# Main_Board.net
KiCad netlist of a schematic drawn in EAGLE
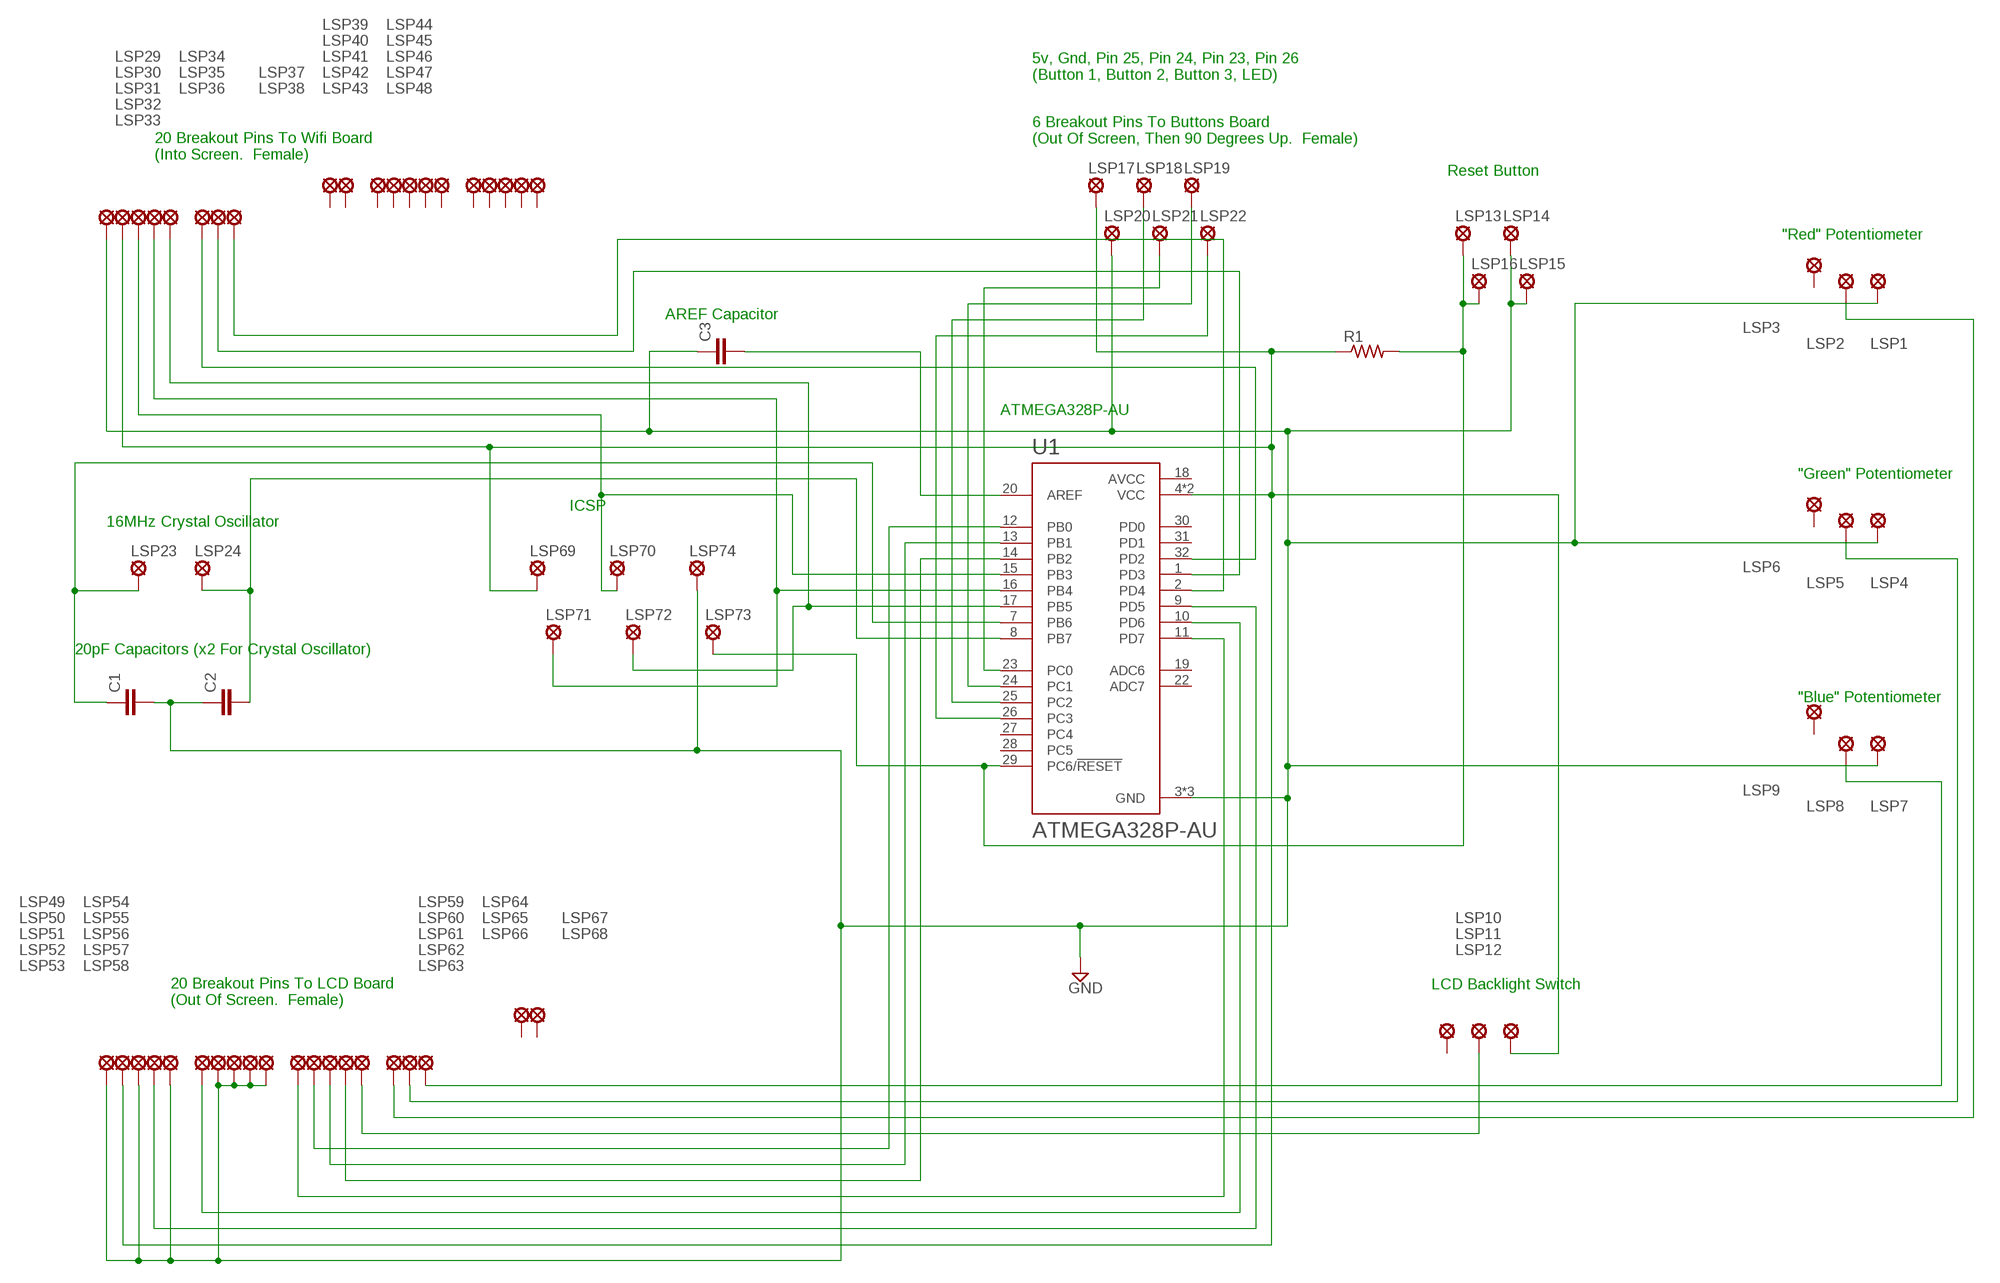
[diagram p0: schematic, sheet 1]

(export (version "E")
  (design (tool "Eeschema 10.0.6"))
  (components
    (comp (ref "C1")
      (value "C5/2.5")
      (footprint "eagle-import:C5B2.5")
      (libsource (lib "eagle-import") (part "C5/2.5"))
    )
    (comp (ref "C2")
      (value "C5/2.5")
      (footprint "eagle-import:C5B2.5")
      (libsource (lib "eagle-import") (part "C5/2.5"))
    )
    (comp (ref "C3")
      (value "C5/2.5")
      (footprint "eagle-import:C5B2.5")
      (libsource (lib "eagle-import") (part "C5/2.5"))
    )
    (comp (ref "LSP1")
      (value "LSP10_CLSP10_C")
      (footprint "eagle-import:LSP10_C")
      (libsource (lib "eagle-import") (part "LSP10_CLSP10_C"))
    )
    (comp (ref "LSP2")
      (value "LSP10_CLSP10_C")
      (footprint "eagle-import:LSP10_C")
      (libsource (lib "eagle-import") (part "LSP10_CLSP10_C"))
    )
    (comp (ref "LSP3")
      (value "LSP10_CLSP10_C")
      (footprint "eagle-import:LSP10_C")
      (libsource (lib "eagle-import") (part "LSP10_CLSP10_C"))
    )
    (comp (ref "LSP4")
      (value "LSP10_CLSP10_C")
      (footprint "eagle-import:LSP10_C")
      (libsource (lib "eagle-import") (part "LSP10_CLSP10_C"))
    )
    (comp (ref "LSP5")
      (value "LSP10_CLSP10_C")
      (footprint "eagle-import:LSP10_C")
      (libsource (lib "eagle-import") (part "LSP10_CLSP10_C"))
    )
    (comp (ref "LSP6")
      (value "LSP10_CLSP10_C")
      (footprint "eagle-import:LSP10_C")
      (libsource (lib "eagle-import") (part "LSP10_CLSP10_C"))
    )
    (comp (ref "LSP7")
      (value "LSP10_CLSP10_C")
      (footprint "eagle-import:LSP10_C")
      (libsource (lib "eagle-import") (part "LSP10_CLSP10_C"))
    )
    (comp (ref "LSP8")
      (value "LSP10_CLSP10_C")
      (footprint "eagle-import:LSP10_C")
      (libsource (lib "eagle-import") (part "LSP10_CLSP10_C"))
    )
    (comp (ref "LSP9")
      (value "LSP10_CLSP10_C")
      (footprint "eagle-import:LSP10_C")
      (libsource (lib "eagle-import") (part "LSP10_CLSP10_C"))
    )
    (comp (ref "LSP10")
      (value "LSP10_CLSP10_C")
      (footprint "eagle-import:LSP10_C")
      (libsource (lib "eagle-import") (part "LSP10_CLSP10_C"))
    )
    (comp (ref "LSP11")
      (value "LSP10_CLSP10_C")
      (footprint "eagle-import:LSP10_C")
      (libsource (lib "eagle-import") (part "LSP10_CLSP10_C"))
    )
    (comp (ref "LSP12")
      (value "LSP10_CLSP10_C")
      (footprint "eagle-import:LSP10_C")
      (libsource (lib "eagle-import") (part "LSP10_CLSP10_C"))
    )
    (comp (ref "LSP13")
      (value "LSP10_CLSP10_C")
      (footprint "eagle-import:LSP10_C")
      (libsource (lib "eagle-import") (part "LSP10_CLSP10_C"))
    )
    (comp (ref "LSP14")
      (value "LSP10_CLSP10_C")
      (footprint "eagle-import:LSP10_C")
      (libsource (lib "eagle-import") (part "LSP10_CLSP10_C"))
    )
    (comp (ref "LSP15")
      (value "LSP10_CLSP10_C")
      (footprint "eagle-import:LSP10_C")
      (libsource (lib "eagle-import") (part "LSP10_CLSP10_C"))
    )
    (comp (ref "LSP16")
      (value "LSP10_CLSP10_C")
      (footprint "eagle-import:LSP10_C")
      (libsource (lib "eagle-import") (part "LSP10_CLSP10_C"))
    )
    (comp (ref "LSP17")
      (value "LSP10_CLSP10_C")
      (footprint "eagle-import:LSP10_C")
      (libsource (lib "eagle-import") (part "LSP10_CLSP10_C"))
    )
    (comp (ref "LSP18")
      (value "LSP10_CLSP10_C")
      (footprint "eagle-import:LSP10_C")
      (libsource (lib "eagle-import") (part "LSP10_CLSP10_C"))
    )
    (comp (ref "LSP19")
      (value "LSP10_CLSP10_C")
      (footprint "eagle-import:LSP10_C")
      (libsource (lib "eagle-import") (part "LSP10_CLSP10_C"))
    )
    (comp (ref "LSP20")
      (value "LSP10_CLSP10_C")
      (footprint "eagle-import:LSP10_C")
      (libsource (lib "eagle-import") (part "LSP10_CLSP10_C"))
    )
    (comp (ref "LSP21")
      (value "LSP10_CLSP10_C")
      (footprint "eagle-import:LSP10_C")
      (libsource (lib "eagle-import") (part "LSP10_CLSP10_C"))
    )
    (comp (ref "LSP22")
      (value "LSP10_CLSP10_C")
      (footprint "eagle-import:LSP10_C")
      (libsource (lib "eagle-import") (part "LSP10_CLSP10_C"))
    )
    (comp (ref "LSP23")
      (value "LSP10_CLSP10_C")
      (footprint "eagle-import:LSP10_C")
      (libsource (lib "eagle-import") (part "LSP10_CLSP10_C"))
    )
    (comp (ref "LSP24")
      (value "LSP10_CLSP10_C")
      (footprint "eagle-import:LSP10_C")
      (libsource (lib "eagle-import") (part "LSP10_CLSP10_C"))
    )
    (comp (ref "LSP29")
      (value "LSP10_CLSP10_C")
      (footprint "eagle-import:LSP10_C")
      (libsource (lib "eagle-import") (part "LSP10_CLSP10_C"))
    )
    (comp (ref "LSP30")
      (value "LSP10_CLSP10_C")
      (footprint "eagle-import:LSP10_C")
      (libsource (lib "eagle-import") (part "LSP10_CLSP10_C"))
    )
    (comp (ref "LSP31")
      (value "LSP10_CLSP10_C")
      (footprint "eagle-import:LSP10_C")
      (libsource (lib "eagle-import") (part "LSP10_CLSP10_C"))
    )
    (comp (ref "LSP32")
      (value "LSP10_CLSP10_C")
      (footprint "eagle-import:LSP10_C")
      (libsource (lib "eagle-import") (part "LSP10_CLSP10_C"))
    )
    (comp (ref "LSP33")
      (value "LSP10_CLSP10_C")
      (footprint "eagle-import:LSP10_C")
      (libsource (lib "eagle-import") (part "LSP10_CLSP10_C"))
    )
    (comp (ref "LSP34")
      (value "LSP10_CLSP10_C")
      (footprint "eagle-import:LSP10_C")
      (libsource (lib "eagle-import") (part "LSP10_CLSP10_C"))
    )
    (comp (ref "LSP35")
      (value "LSP10_CLSP10_C")
      (footprint "eagle-import:LSP10_C")
      (libsource (lib "eagle-import") (part "LSP10_CLSP10_C"))
    )
    (comp (ref "LSP36")
      (value "LSP10_CLSP10_C")
      (footprint "eagle-import:LSP10_C")
      (libsource (lib "eagle-import") (part "LSP10_CLSP10_C"))
    )
    (comp (ref "LSP37")
      (value "LSP10_CLSP10_C")
      (footprint "eagle-import:LSP10_C")
      (libsource (lib "eagle-import") (part "LSP10_CLSP10_C"))
    )
    (comp (ref "LSP38")
      (value "LSP10_CLSP10_C")
      (footprint "eagle-import:LSP10_C")
      (libsource (lib "eagle-import") (part "LSP10_CLSP10_C"))
    )
    (comp (ref "LSP39")
      (value "LSP10_CLSP10_C")
      (footprint "eagle-import:LSP10_C")
      (libsource (lib "eagle-import") (part "LSP10_CLSP10_C"))
    )
    (comp (ref "LSP40")
      (value "LSP10_CLSP10_C")
      (footprint "eagle-import:LSP10_C")
      (libsource (lib "eagle-import") (part "LSP10_CLSP10_C"))
    )
    (comp (ref "LSP41")
      (value "LSP10_CLSP10_C")
      (footprint "eagle-import:LSP10_C")
      (libsource (lib "eagle-import") (part "LSP10_CLSP10_C"))
    )
    (comp (ref "LSP42")
      (value "LSP10_CLSP10_C")
      (footprint "eagle-import:LSP10_C")
      (libsource (lib "eagle-import") (part "LSP10_CLSP10_C"))
    )
    (comp (ref "LSP43")
      (value "LSP10_CLSP10_C")
      (footprint "eagle-import:LSP10_C")
      (libsource (lib "eagle-import") (part "LSP10_CLSP10_C"))
    )
    (comp (ref "LSP44")
      (value "LSP10_CLSP10_C")
      (footprint "eagle-import:LSP10_C")
      (libsource (lib "eagle-import") (part "LSP10_CLSP10_C"))
    )
    (comp (ref "LSP45")
      (value "LSP10_CLSP10_C")
      (footprint "eagle-import:LSP10_C")
      (libsource (lib "eagle-import") (part "LSP10_CLSP10_C"))
    )
    (comp (ref "LSP46")
      (value "LSP10_CLSP10_C")
      (footprint "eagle-import:LSP10_C")
      (libsource (lib "eagle-import") (part "LSP10_CLSP10_C"))
    )
    (comp (ref "LSP47")
      (value "LSP10_CLSP10_C")
      (footprint "eagle-import:LSP10_C")
      (libsource (lib "eagle-import") (part "LSP10_CLSP10_C"))
    )
    (comp (ref "LSP48")
      (value "LSP10_CLSP10_C")
      (footprint "eagle-import:LSP10_C")
      (libsource (lib "eagle-import") (part "LSP10_CLSP10_C"))
    )
    (comp (ref "LSP49")
      (value "LSP10_CLSP10_C")
      (footprint "eagle-import:LSP10_C")
      (libsource (lib "eagle-import") (part "LSP10_CLSP10_C"))
    )
    (comp (ref "LSP50")
      (value "LSP10_CLSP10_C")
      (footprint "eagle-import:LSP10_C")
      (libsource (lib "eagle-import") (part "LSP10_CLSP10_C"))
    )
    (comp (ref "LSP51")
      (value "LSP10_CLSP10_C")
      (footprint "eagle-import:LSP10_C")
      (libsource (lib "eagle-import") (part "LSP10_CLSP10_C"))
    )
    (comp (ref "LSP52")
      (value "LSP10_CLSP10_C")
      (footprint "eagle-import:LSP10_C")
      (libsource (lib "eagle-import") (part "LSP10_CLSP10_C"))
    )
    (comp (ref "LSP53")
      (value "LSP10_CLSP10_C")
      (footprint "eagle-import:LSP10_C")
      (libsource (lib "eagle-import") (part "LSP10_CLSP10_C"))
    )
    (comp (ref "LSP54")
      (value "LSP10_CLSP10_C")
      (footprint "eagle-import:LSP10_C")
      (libsource (lib "eagle-import") (part "LSP10_CLSP10_C"))
    )
    (comp (ref "LSP55")
      (value "LSP10_CLSP10_C")
      (footprint "eagle-import:LSP10_C")
      (libsource (lib "eagle-import") (part "LSP10_CLSP10_C"))
    )
    (comp (ref "LSP56")
      (value "LSP10_CLSP10_C")
      (footprint "eagle-import:LSP10_C")
      (libsource (lib "eagle-import") (part "LSP10_CLSP10_C"))
    )
    (comp (ref "LSP57")
      (value "LSP10_CLSP10_C")
      (footprint "eagle-import:LSP10_C")
      (libsource (lib "eagle-import") (part "LSP10_CLSP10_C"))
    )
    (comp (ref "LSP58")
      (value "LSP10_CLSP10_C")
      (footprint "eagle-import:LSP10_C")
      (libsource (lib "eagle-import") (part "LSP10_CLSP10_C"))
    )
    (comp (ref "LSP59")
      (value "LSP10_CLSP10_C")
      (footprint "eagle-import:LSP10_C")
      (libsource (lib "eagle-import") (part "LSP10_CLSP10_C"))
    )
    (comp (ref "LSP60")
      (value "LSP10_CLSP10_C")
      (footprint "eagle-import:LSP10_C")
      (libsource (lib "eagle-import") (part "LSP10_CLSP10_C"))
    )
    (comp (ref "LSP61")
      (value "LSP10_CLSP10_C")
      (footprint "eagle-import:LSP10_C")
      (libsource (lib "eagle-import") (part "LSP10_CLSP10_C"))
    )
    (comp (ref "LSP62")
      (value "LSP10_CLSP10_C")
      (footprint "eagle-import:LSP10_C")
      (libsource (lib "eagle-import") (part "LSP10_CLSP10_C"))
    )
    (comp (ref "LSP63")
      (value "LSP10_CLSP10_C")
      (footprint "eagle-import:LSP10_C")
      (libsource (lib "eagle-import") (part "LSP10_CLSP10_C"))
    )
    (comp (ref "LSP64")
      (value "LSP10_CLSP10_C")
      (footprint "eagle-import:LSP10_C")
      (libsource (lib "eagle-import") (part "LSP10_CLSP10_C"))
    )
    (comp (ref "LSP65")
      (value "LSP10_CLSP10_C")
      (footprint "eagle-import:LSP10_C")
      (libsource (lib "eagle-import") (part "LSP10_CLSP10_C"))
    )
    (comp (ref "LSP66")
      (value "LSP10_CLSP10_C")
      (footprint "eagle-import:LSP10_C")
      (libsource (lib "eagle-import") (part "LSP10_CLSP10_C"))
    )
    (comp (ref "LSP67")
      (value "LSP10_CLSP10_C")
      (footprint "eagle-import:LSP10_C")
      (libsource (lib "eagle-import") (part "LSP10_CLSP10_C"))
    )
    (comp (ref "LSP68")
      (value "LSP10_CLSP10_C")
      (footprint "eagle-import:LSP10_C")
      (libsource (lib "eagle-import") (part "LSP10_CLSP10_C"))
    )
    (comp (ref "LSP69")
      (value "LSP10_CLSP10_C")
      (footprint "eagle-import:LSP10_C")
      (libsource (lib "eagle-import") (part "LSP10_CLSP10_C"))
    )
    (comp (ref "LSP70")
      (value "LSP10_CLSP10_C")
      (footprint "eagle-import:LSP10_C")
      (libsource (lib "eagle-import") (part "LSP10_CLSP10_C"))
    )
    (comp (ref "LSP71")
      (value "LSP10_CLSP10_C")
      (footprint "eagle-import:LSP10_C")
      (libsource (lib "eagle-import") (part "LSP10_CLSP10_C"))
    )
    (comp (ref "LSP72")
      (value "LSP10_CLSP10_C")
      (footprint "eagle-import:LSP10_C")
      (libsource (lib "eagle-import") (part "LSP10_CLSP10_C"))
    )
    (comp (ref "LSP73")
      (value "LSP10_CLSP10_C")
      (footprint "eagle-import:LSP10_C")
      (libsource (lib "eagle-import") (part "LSP10_CLSP10_C"))
    )
    (comp (ref "LSP74")
      (value "LSP10_CLSP10_C")
      (footprint "eagle-import:LSP10_C")
      (libsource (lib "eagle-import") (part "LSP10_CLSP10_C"))
    )
    (comp (ref "R1")
      (value "R-US_VMTA55")
      (footprint "eagle-import:VMTA55")
      (libsource (lib "eagle-import") (part "R-US_VMTA55"))
    )
    (comp (ref "U1")
      (value "ATMEGA328P-AU")
      (footprint "eagle-import:QFP80P900X900X120-32N")
      (fields (field (name "MF") "Microchip"))
      (libsource (lib "eagle-import") (part "ATMEGA328P-AU"))
    )
  )
  (nets
    (net (code "1") (name "/AVCC") (class "Default")
      (node (ref "U1") (pin "18") (pinfunction "AVCC_18") (pintype "power_in"))
    )
    (net (code "2") (name "GND") (class "Default")
      (node (ref "C1") (pin "2") (pinfunction "2_2") (pintype "passive"))
      (node (ref "C2") (pin "1") (pinfunction "1_1") (pintype "passive"))
      (node (ref "C3") (pin "1") (pinfunction "1_1") (pintype "passive"))
      (node (ref "LSP1") (pin "P$1") (pinfunction "MP_P$1") (pintype "passive"))
      (node (ref "LSP14") (pin "P$1") (pinfunction "MP_P$1") (pintype "passive"))
      (node (ref "LSP15") (pin "P$1") (pinfunction "MP_P$1") (pintype "passive"))
      (node (ref "LSP20") (pin "P$1") (pinfunction "MP_P$1") (pintype "passive"))
      (node (ref "LSP29") (pin "P$1") (pinfunction "MP_P$1") (pintype "passive"))
      (node (ref "LSP4") (pin "P$1") (pinfunction "MP_P$1") (pintype "passive"))
      (node (ref "LSP49") (pin "P$1") (pinfunction "MP_P$1") (pintype "passive"))
      (node (ref "LSP51") (pin "P$1") (pinfunction "MP_P$1") (pintype "passive"))
      (node (ref "LSP53") (pin "P$1") (pinfunction "MP_P$1") (pintype "passive"))
      (node (ref "LSP55") (pin "P$1") (pinfunction "MP_P$1") (pintype "passive"))
      (node (ref "LSP56") (pin "P$1") (pinfunction "MP_P$1") (pintype "passive"))
      (node (ref "LSP57") (pin "P$1") (pinfunction "MP_P$1") (pintype "passive"))
      (node (ref "LSP58") (pin "P$1") (pinfunction "MP_P$1") (pintype "passive"))
      (node (ref "LSP7") (pin "P$1") (pinfunction "MP_P$1") (pintype "passive"))
      (node (ref "LSP74") (pin "P$1") (pinfunction "MP_P$1") (pintype "passive"))
      (node (ref "U1") (pin "21") (pinfunction "GND_21") (pintype "power_in"))
      (node (ref "U1") (pin "3") (pinfunction "GND_3") (pintype "power_in"))
      (node (ref "U1") (pin "5") (pinfunction "GND_5") (pintype "power_in"))
    )
    (net (code "3") (name "Net-(LSP2-MP)") (class "Default")
      (node (ref "LSP2") (pin "P$1") (pinfunction "MP_P$1") (pintype "passive"))
      (node (ref "LSP64") (pin "P$1") (pinfunction "MP_P$1") (pintype "passive"))
    )
    (net (code "4") (name "Net-(LSP5-MP)") (class "Default")
      (node (ref "LSP5") (pin "P$1") (pinfunction "MP_P$1") (pintype "passive"))
      (node (ref "LSP65") (pin "P$1") (pinfunction "MP_P$1") (pintype "passive"))
    )
    (net (code "5") (name "Net-(LSP11-MP)") (class "Default")
      (node (ref "LSP11") (pin "P$1") (pinfunction "MP_P$1") (pintype "passive"))
      (node (ref "LSP63") (pin "P$1") (pinfunction "MP_P$1") (pintype "passive"))
    )
    (net (code "6") (name "Net-(LSP12-MP)") (class "Default")
      (node (ref "LSP12") (pin "P$1") (pinfunction "MP_P$1") (pintype "passive"))
      (node (ref "LSP17") (pin "P$1") (pinfunction "MP_P$1") (pintype "passive"))
      (node (ref "LSP30") (pin "P$1") (pinfunction "MP_P$1") (pintype "passive"))
      (node (ref "LSP50") (pin "P$1") (pinfunction "MP_P$1") (pintype "passive"))
      (node (ref "LSP69") (pin "P$1") (pinfunction "MP_P$1") (pintype "passive"))
      (node (ref "R1") (pin "1") (pinfunction "1_1") (pintype "passive"))
      (node (ref "U1") (pin "4") (pinfunction "VCC_4") (pintype "power_in"))
      (node (ref "U1") (pin "6") (pinfunction "VCC_6") (pintype "power_in"))
    )
    (net (code "7") (name "Net-(LSP13-MP)") (class "Default")
      (node (ref "LSP13") (pin "P$1") (pinfunction "MP_P$1") (pintype "passive"))
      (node (ref "LSP16") (pin "P$1") (pinfunction "MP_P$1") (pintype "passive"))
      (node (ref "LSP73") (pin "P$1") (pinfunction "MP_P$1") (pintype "passive"))
      (node (ref "R1") (pin "2") (pinfunction "2_2") (pintype "passive"))
      (node (ref "U1") (pin "29") (pinfunction "PC6/~{RESET}_29") (pintype "bidirectional"))
    )
    (net (code "8") (name "Net-(LSP18-MP)") (class "Default")
      (node (ref "LSP18") (pin "P$1") (pinfunction "MP_P$1") (pintype "passive"))
      (node (ref "U1") (pin "25") (pinfunction "PC2_25") (pintype "bidirectional"))
    )
    (net (code "9") (name "Net-(LSP19-MP)") (class "Default")
      (node (ref "LSP19") (pin "P$1") (pinfunction "MP_P$1") (pintype "passive"))
      (node (ref "U1") (pin "24") (pinfunction "PC1_24") (pintype "bidirectional"))
    )
    (net (code "10") (name "Net-(LSP21-MP)") (class "Default")
      (node (ref "LSP21") (pin "P$1") (pinfunction "MP_P$1") (pintype "passive"))
      (node (ref "U1") (pin "23") (pinfunction "PC0_23") (pintype "bidirectional"))
    )
    (net (code "11") (name "Net-(LSP22-MP)") (class "Default")
      (node (ref "LSP22") (pin "P$1") (pinfunction "MP_P$1") (pintype "passive"))
      (node (ref "U1") (pin "26") (pinfunction "PC3_26") (pintype "bidirectional"))
    )
    (net (code "12") (name "Net-(LSP23-MP)") (class "Default")
      (node (ref "C1") (pin "1") (pinfunction "1_1") (pintype "passive"))
      (node (ref "LSP23") (pin "P$1") (pinfunction "MP_P$1") (pintype "passive"))
      (node (ref "U1") (pin "7") (pinfunction "PB6_7") (pintype "bidirectional"))
    )
    (net (code "13") (name "Net-(LSP24-MP)") (class "Default")
      (node (ref "C2") (pin "2") (pinfunction "2_2") (pintype "passive"))
      (node (ref "LSP24") (pin "P$1") (pinfunction "MP_P$1") (pintype "passive"))
      (node (ref "U1") (pin "8") (pinfunction "PB7_8") (pintype "bidirectional"))
    )
    (net (code "14") (name "Net-(LSP31-MP)") (class "Default")
      (node (ref "LSP31") (pin "P$1") (pinfunction "MP_P$1") (pintype "passive"))
      (node (ref "LSP70") (pin "P$1") (pinfunction "MP_P$1") (pintype "passive"))
      (node (ref "U1") (pin "15") (pinfunction "PB3_15") (pintype "bidirectional"))
    )
    (net (code "15") (name "Net-(LSP32-MP)") (class "Default")
      (node (ref "LSP32") (pin "P$1") (pinfunction "MP_P$1") (pintype "passive"))
      (node (ref "LSP71") (pin "P$1") (pinfunction "MP_P$1") (pintype "passive"))
      (node (ref "U1") (pin "16") (pinfunction "PB4_16") (pintype "bidirectional"))
    )
    (net (code "16") (name "Net-(LSP33-MP)") (class "Default")
      (node (ref "LSP33") (pin "P$1") (pinfunction "MP_P$1") (pintype "passive"))
      (node (ref "LSP72") (pin "P$1") (pinfunction "MP_P$1") (pintype "passive"))
      (node (ref "U1") (pin "17") (pinfunction "PB5_17") (pintype "bidirectional"))
    )
    (net (code "17") (name "Net-(LSP34-MP)") (class "Default")
      (node (ref "LSP34") (pin "P$1") (pinfunction "MP_P$1") (pintype "passive"))
      (node (ref "U1") (pin "32") (pinfunction "PD2_32") (pintype "bidirectional"))
    )
    (net (code "18") (name "Net-(LSP35-MP)") (class "Default")
      (node (ref "LSP35") (pin "P$1") (pinfunction "MP_P$1") (pintype "passive"))
      (node (ref "U1") (pin "1") (pinfunction "PD3_1") (pintype "bidirectional"))
    )
    (net (code "19") (name "Net-(LSP36-MP)") (class "Default")
      (node (ref "LSP36") (pin "P$1") (pinfunction "MP_P$1") (pintype "passive"))
      (node (ref "U1") (pin "2") (pinfunction "PD4_2") (pintype "bidirectional"))
    )
    (net (code "20") (name "Net-(LSP52-MP)") (class "Default")
      (node (ref "LSP52") (pin "P$1") (pinfunction "MP_P$1") (pintype "passive"))
      (node (ref "U1") (pin "9") (pinfunction "PD5_9") (pintype "bidirectional"))
    )
    (net (code "21") (name "Net-(LSP54-MP)") (class "Default")
      (node (ref "LSP54") (pin "P$1") (pinfunction "MP_P$1") (pintype "passive"))
      (node (ref "U1") (pin "10") (pinfunction "PD6_10") (pintype "bidirectional"))
    )
    (net (code "22") (name "Net-(LSP59-MP)") (class "Default")
      (node (ref "LSP59") (pin "P$1") (pinfunction "MP_P$1") (pintype "passive"))
      (node (ref "U1") (pin "11") (pinfunction "PD7_11") (pintype "bidirectional"))
    )
    (net (code "23") (name "Net-(LSP60-MP)") (class "Default")
      (node (ref "LSP60") (pin "P$1") (pinfunction "MP_P$1") (pintype "passive"))
      (node (ref "U1") (pin "12") (pinfunction "PB0_12") (pintype "bidirectional"))
    )
    (net (code "24") (name "Net-(LSP61-MP)") (class "Default")
      (node (ref "LSP61") (pin "P$1") (pinfunction "MP_P$1") (pintype "passive"))
      (node (ref "U1") (pin "13") (pinfunction "PB1_13") (pintype "bidirectional"))
    )
    (net (code "25") (name "Net-(LSP62-MP)") (class "Default")
      (node (ref "LSP62") (pin "P$1") (pinfunction "MP_P$1") (pintype "passive"))
      (node (ref "U1") (pin "14") (pinfunction "PB2_14") (pintype "bidirectional"))
    )
    (net (code "26") (name "Net-(LSP66-MP)") (class "Default")
      (node (ref "LSP66") (pin "P$1") (pinfunction "MP_P$1") (pintype "passive"))
      (node (ref "LSP8") (pin "P$1") (pinfunction "MP_P$1") (pintype "passive"))
    )
    (net (code "27") (name "Net-(U1-AREF)") (class "Default")
      (node (ref "C3") (pin "2") (pinfunction "2_2") (pintype "passive"))
      (node (ref "U1") (pin "20") (pinfunction "AREF_20") (pintype "input"))
    )
    (net (code "28") (name "unconnected-(LSP3-MP-PadP$1)") (class "Default")
      (node (ref "LSP3") (pin "P$1") (pinfunction "MP_P$1") (pintype "passive"))
    )
    (net (code "29") (name "unconnected-(LSP6-MP-PadP$1)") (class "Default")
      (node (ref "LSP6") (pin "P$1") (pinfunction "MP_P$1") (pintype "passive"))
    )
    (net (code "30") (name "unconnected-(LSP9-MP-PadP$1)") (class "Default")
      (node (ref "LSP9") (pin "P$1") (pinfunction "MP_P$1") (pintype "passive"))
    )
    (net (code "31") (name "unconnected-(LSP10-MP-PadP$1)") (class "Default")
      (node (ref "LSP10") (pin "P$1") (pinfunction "MP_P$1") (pintype "passive"))
    )
    (net (code "32") (name "unconnected-(LSP37-MP-PadP$1)") (class "Default")
      (node (ref "LSP37") (pin "P$1") (pinfunction "MP_P$1") (pintype "passive"))
    )
    (net (code "33") (name "unconnected-(LSP38-MP-PadP$1)") (class "Default")
      (node (ref "LSP38") (pin "P$1") (pinfunction "MP_P$1") (pintype "passive"))
    )
    (net (code "34") (name "unconnected-(LSP39-MP-PadP$1)") (class "Default")
      (node (ref "LSP39") (pin "P$1") (pinfunction "MP_P$1") (pintype "passive"))
    )
    (net (code "35") (name "unconnected-(LSP40-MP-PadP$1)") (class "Default")
      (node (ref "LSP40") (pin "P$1") (pinfunction "MP_P$1") (pintype "passive"))
    )
    (net (code "36") (name "unconnected-(LSP41-MP-PadP$1)") (class "Default")
      (node (ref "LSP41") (pin "P$1") (pinfunction "MP_P$1") (pintype "passive"))
    )
    (net (code "37") (name "unconnected-(LSP42-MP-PadP$1)") (class "Default")
      (node (ref "LSP42") (pin "P$1") (pinfunction "MP_P$1") (pintype "passive"))
    )
    (net (code "38") (name "unconnected-(LSP43-MP-PadP$1)") (class "Default")
      (node (ref "LSP43") (pin "P$1") (pinfunction "MP_P$1") (pintype "passive"))
    )
    (net (code "39") (name "unconnected-(LSP44-MP-PadP$1)") (class "Default")
      (node (ref "LSP44") (pin "P$1") (pinfunction "MP_P$1") (pintype "passive"))
    )
    (net (code "40") (name "unconnected-(LSP45-MP-PadP$1)") (class "Default")
      (node (ref "LSP45") (pin "P$1") (pinfunction "MP_P$1") (pintype "passive"))
    )
    (net (code "41") (name "unconnected-(LSP46-MP-PadP$1)") (class "Default")
      (node (ref "LSP46") (pin "P$1") (pinfunction "MP_P$1") (pintype "passive"))
    )
    (net (code "42") (name "unconnected-(LSP47-MP-PadP$1)") (class "Default")
      (node (ref "LSP47") (pin "P$1") (pinfunction "MP_P$1") (pintype "passive"))
    )
    (net (code "43") (name "unconnected-(LSP48-MP-PadP$1)") (class "Default")
      (node (ref "LSP48") (pin "P$1") (pinfunction "MP_P$1") (pintype "passive"))
    )
    (net (code "44") (name "unconnected-(LSP67-MP-PadP$1)") (class "Default")
      (node (ref "LSP67") (pin "P$1") (pinfunction "MP_P$1") (pintype "passive"))
    )
    (net (code "45") (name "unconnected-(LSP68-MP-PadP$1)") (class "Default")
      (node (ref "LSP68") (pin "P$1") (pinfunction "MP_P$1") (pintype "passive"))
    )
    (net (code "46") (name "unconnected-(U1-ADC6-Pad19)") (class "Default")
      (node (ref "U1") (pin "19") (pinfunction "ADC6_19") (pintype "bidirectional"))
    )
    (net (code "47") (name "unconnected-(U1-ADC7-Pad22)") (class "Default")
      (node (ref "U1") (pin "22") (pinfunction "ADC7_22") (pintype "bidirectional"))
    )
    (net (code "48") (name "unconnected-(U1-PC4-Pad27)") (class "Default")
      (node (ref "U1") (pin "27") (pinfunction "PC4_27") (pintype "bidirectional"))
    )
    (net (code "49") (name "unconnected-(U1-PC5-Pad28)") (class "Default")
      (node (ref "U1") (pin "28") (pinfunction "PC5_28") (pintype "bidirectional"))
    )
    (net (code "50") (name "unconnected-(U1-PD0-Pad30)") (class "Default")
      (node (ref "U1") (pin "30") (pinfunction "PD0_30") (pintype "bidirectional"))
    )
    (net (code "51") (name "unconnected-(U1-PD1-Pad31)") (class "Default")
      (node (ref "U1") (pin "31") (pinfunction "PD1_31") (pintype "bidirectional"))
    )
  )
)
